# MICROCONTROLLER.net
KiCad netlist of a schematic drawn in Altium Designer
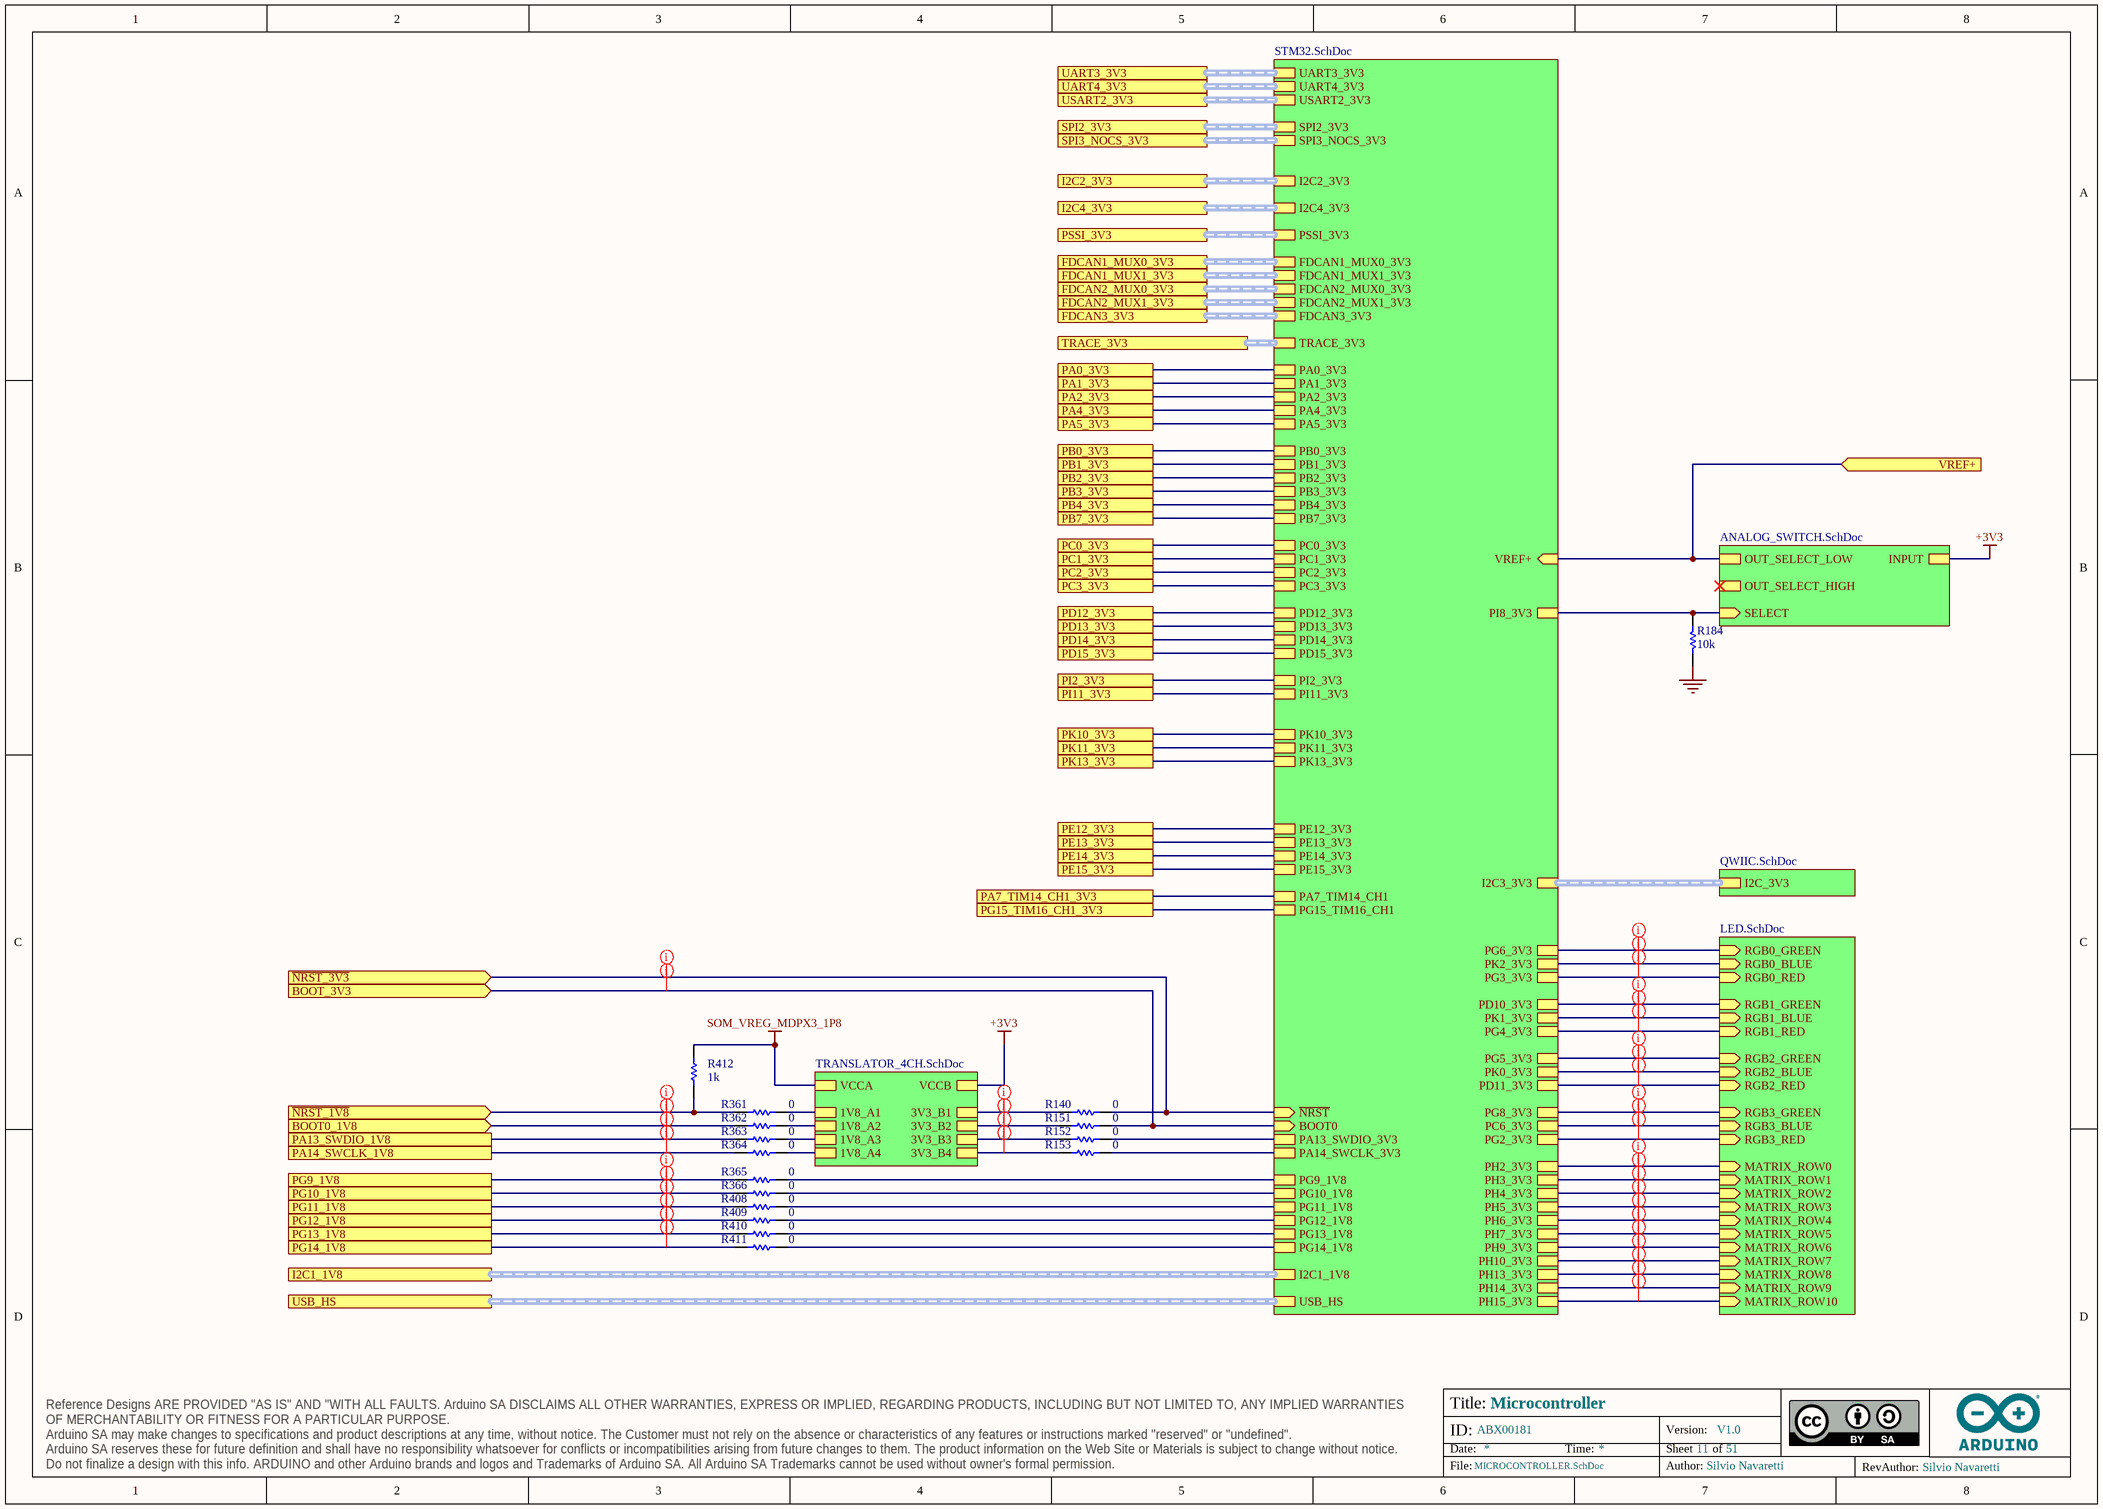
[diagram p0: MICROCONTROLLER.SchDoc]

(export (version "E")
  (design (tool "Eeschema 10.0.6"))
  (components
    (comp (ref "R140")
      (value "0")
      (footprint "RES-0201")
      (description "RES CHIP 0201 0R")
      (fields (field (name "MANUFACTURER") "Vishay") (field (name "PART NUMBER") "CRCW02010000Z0ED"))
      (libsource (lib "Clean") (part "RES"))
    )
    (comp (ref "R151")
      (value "0")
      (footprint "RES-0201")
      (description "RES CHIP 0201 0R")
      (fields (field (name "MANUFACTURER") "Vishay") (field (name "PART NUMBER") "CRCW02010000Z0ED"))
      (libsource (lib "Clean") (part "RES"))
    )
    (comp (ref "R152")
      (value "0")
      (footprint "RES-0201")
      (description "RES CHIP 0201 0R")
      (fields (field (name "MANUFACTURER") "Vishay") (field (name "PART NUMBER") "CRCW02010000Z0ED"))
      (libsource (lib "Clean") (part "RES"))
    )
    (comp (ref "R153")
      (value "0")
      (footprint "RES-0201")
      (description "RES CHIP 0201 0R")
      (fields (field (name "MANUFACTURER") "Vishay") (field (name "PART NUMBER") "CRCW02010000Z0ED"))
      (libsource (lib "Clean") (part "RES"))
    )
    (comp (ref "R184")
      (value "10k")
      (footprint "RES-0201")
      (description "RES CHIP 0201 10k 1% 1/20W")
      (fields (field (name "POWER") "50mW") (field (name "TOLERANCE") "1%"))
      (libsource (lib "Clean") (part "RES"))
    )
    (comp (ref "R361")
      (value "0")
      (footprint "RES-0201")
      (description "RES CHIP 0201 0R")
      (fields (field (name "MANUFACTURER") "Vishay") (field (name "PART NUMBER") "CRCW02010000Z0ED"))
      (libsource (lib "Clean") (part "RES"))
    )
    (comp (ref "R362")
      (value "0")
      (footprint "RES-0201")
      (description "RES CHIP 0201 0R")
      (fields (field (name "MANUFACTURER") "Vishay") (field (name "PART NUMBER") "CRCW02010000Z0ED"))
      (libsource (lib "Clean") (part "RES"))
    )
    (comp (ref "R363")
      (value "0")
      (footprint "RES-0201")
      (description "RES CHIP 0201 0R")
      (fields (field (name "MANUFACTURER") "Vishay") (field (name "PART NUMBER") "CRCW02010000Z0ED"))
      (libsource (lib "Clean") (part "RES"))
    )
    (comp (ref "R364")
      (value "0")
      (footprint "RES-0201")
      (description "RES CHIP 0201 0R")
      (fields (field (name "MANUFACTURER") "Vishay") (field (name "PART NUMBER") "CRCW02010000Z0ED"))
      (libsource (lib "Clean") (part "RES"))
    )
    (comp (ref "R365")
      (value "0")
      (footprint "RES-0201")
      (description "RES CHIP 0201 0R")
      (fields (field (name "MANUFACTURER") "Vishay") (field (name "PART NUMBER") "CRCW02010000Z0ED"))
      (libsource (lib "Clean") (part "RES"))
    )
    (comp (ref "R366")
      (value "0")
      (footprint "RES-0201")
      (description "RES CHIP 0201 0R")
      (fields (field (name "MANUFACTURER") "Vishay") (field (name "PART NUMBER") "CRCW02010000Z0ED"))
      (libsource (lib "Clean") (part "RES"))
    )
    (comp (ref "R408")
      (value "0")
      (footprint "RES-0201")
      (description "RES CHIP 0201 0R")
      (fields (field (name "MANUFACTURER") "Vishay") (field (name "PART NUMBER") "CRCW02010000Z0ED"))
      (libsource (lib "Clean") (part "RES"))
    )
    (comp (ref "R409")
      (value "0")
      (footprint "RES-0201")
      (description "RES CHIP 0201 0R")
      (fields (field (name "MANUFACTURER") "Vishay") (field (name "PART NUMBER") "CRCW02010000Z0ED"))
      (libsource (lib "Clean") (part "RES"))
    )
    (comp (ref "R410")
      (value "0")
      (footprint "RES-0201")
      (description "RES CHIP 0201 0R")
      (fields (field (name "MANUFACTURER") "Vishay") (field (name "PART NUMBER") "CRCW02010000Z0ED"))
      (libsource (lib "Clean") (part "RES"))
    )
    (comp (ref "R411")
      (value "0")
      (footprint "RES-0201")
      (description "RES CHIP 0201 0R")
      (fields (field (name "MANUFACTURER") "Vishay") (field (name "PART NUMBER") "CRCW02010000Z0ED"))
      (libsource (lib "Clean") (part "RES"))
    )
    (comp (ref "R412")
      (value "1k")
      (footprint "RES-0201")
      (description "RES CHIP 0201 1k 1% 1/20W")
      (fields (field (name "POWER") "50mW") (field (name "TOLERANCE") "1%"))
      (libsource (lib "Clean") (part "RES"))
    )
  )
  (nets
    (net (code "2") (name "/1V8_A1") (class "Default")
      (node (ref "R361") (pin "1") (pinfunction "1_1") (pintype "passive"))
    )
    (net (code "3") (name "/1V8_A2") (class "Default")
      (node (ref "R362") (pin "1") (pinfunction "1_1") (pintype "passive"))
    )
    (net (code "4") (name "/1V8_A3") (class "Default")
      (node (ref "R363") (pin "1") (pinfunction "1_1") (pintype "passive"))
    )
    (net (code "5") (name "/1V8_A4") (class "Default")
      (node (ref "R364") (pin "1") (pinfunction "1_1") (pintype "passive"))
    )
    (net (code "6") (name "/3V3_B1") (class "Default")
      (node (ref "R140") (pin "2") (pinfunction "2_2") (pintype "passive"))
    )
    (net (code "7") (name "/3V3_B2") (class "Default")
      (node (ref "R151") (pin "2") (pinfunction "2_2") (pintype "passive"))
    )
    (net (code "8") (name "/3V3_B3") (class "Default")
      (node (ref "R152") (pin "2") (pinfunction "2_2") (pintype "passive"))
    )
    (net (code "9") (name "/3V3_B4") (class "Default")
      (node (ref "R153") (pin "2") (pinfunction "2_2") (pintype "passive"))
    )
    (net (code "10") (name "/BOOT0_1V8") (class "Default")
      (node (ref "R362") (pin "2") (pinfunction "2_2") (pintype "passive"))
    )
    (net (code "11") (name "/BOOT_3V3") (class "Default")
      (node (ref "R151") (pin "1") (pinfunction "1_1") (pintype "passive"))
    )
    (net (code "39") (name "/PA13_SWDIO_1V8") (class "Default")
      (node (ref "R363") (pin "2") (pinfunction "2_2") (pintype "passive"))
    )
    (net (code "40") (name "/PA13_SWDIO_3V3") (class "Default")
      (node (ref "R152") (pin "1") (pinfunction "1_1") (pintype "passive"))
    )
    (net (code "41") (name "/PA14_SWCLK_1V8") (class "Default")
      (node (ref "R364") (pin "2") (pinfunction "2_2") (pintype "passive"))
    )
    (net (code "42") (name "/PA14_SWCLK_3V3") (class "Default")
      (node (ref "R153") (pin "1") (pinfunction "1_1") (pintype "passive"))
    )
    (net (code "70") (name "/PG9_1V8") (class "Default")
      (node (ref "R365") (pin "2") (pinfunction "2_2") (pintype "passive"))
    )
    (net (code "71") (name "/PG9_1V8_1") (class "Default")
      (node (ref "R365") (pin "1") (pinfunction "1_1") (pintype "passive"))
    )
    (net (code "72") (name "/PG10_1V8") (class "Default")
      (node (ref "R366") (pin "2") (pinfunction "2_2") (pintype "passive"))
    )
    (net (code "73") (name "/PG10_1V8_1") (class "Default")
      (node (ref "R366") (pin "1") (pinfunction "1_1") (pintype "passive"))
    )
    (net (code "74") (name "/PG11_1V8") (class "Default")
      (node (ref "R408") (pin "2") (pinfunction "2_2") (pintype "passive"))
    )
    (net (code "75") (name "/PG11_1V8_1") (class "Default")
      (node (ref "R408") (pin "1") (pinfunction "1_1") (pintype "passive"))
    )
    (net (code "76") (name "/PG12_1V8") (class "Default")
      (node (ref "R409") (pin "2") (pinfunction "2_2") (pintype "passive"))
    )
    (net (code "77") (name "/PG12_1V8_1") (class "Default")
      (node (ref "R409") (pin "1") (pinfunction "1_1") (pintype "passive"))
    )
    (net (code "78") (name "/PG13_1V8") (class "Default")
      (node (ref "R410") (pin "2") (pinfunction "2_2") (pintype "passive"))
    )
    (net (code "79") (name "/PG13_1V8_1") (class "Default")
      (node (ref "R410") (pin "1") (pinfunction "1_1") (pintype "passive"))
    )
    (net (code "80") (name "/PG14_1V8") (class "Default")
      (node (ref "R411") (pin "2") (pinfunction "2_2") (pintype "passive"))
    )
    (net (code "81") (name "/PG14_1V8_1") (class "Default")
      (node (ref "R411") (pin "1") (pinfunction "1_1") (pintype "passive"))
    )
    (net (code "84") (name "/PI8_3V3") (class "Default")
      (node (ref "R184") (pin "2") (pinfunction "2_2") (pintype "passive"))
    )
    (net (code "101") (name "/~{NRST_1V8}") (class "Default")
      (node (ref "R361") (pin "2") (pinfunction "2_2") (pintype "passive"))
      (node (ref "R412") (pin "2") (pinfunction "2_2") (pintype "passive"))
    )
    (net (code "102") (name "/~{NRST_3V3}") (class "Default")
      (node (ref "R140") (pin "1") (pinfunction "1_1") (pintype "passive"))
    )
    (net (code "103") (name "GND") (class "Default")
      (node (ref "R184") (pin "1") (pinfunction "1_1") (pintype "passive"))
    )
    (net (code "104") (name "SOM_VREG_MDPX3_1P8") (class "Default")
      (node (ref "R412") (pin "1") (pinfunction "1_1") (pintype "passive"))
    )
  )
)
